# 05_-_SAMA7D65-MPU.net
KiCad netlist of a schematic drawn in Altium Designer
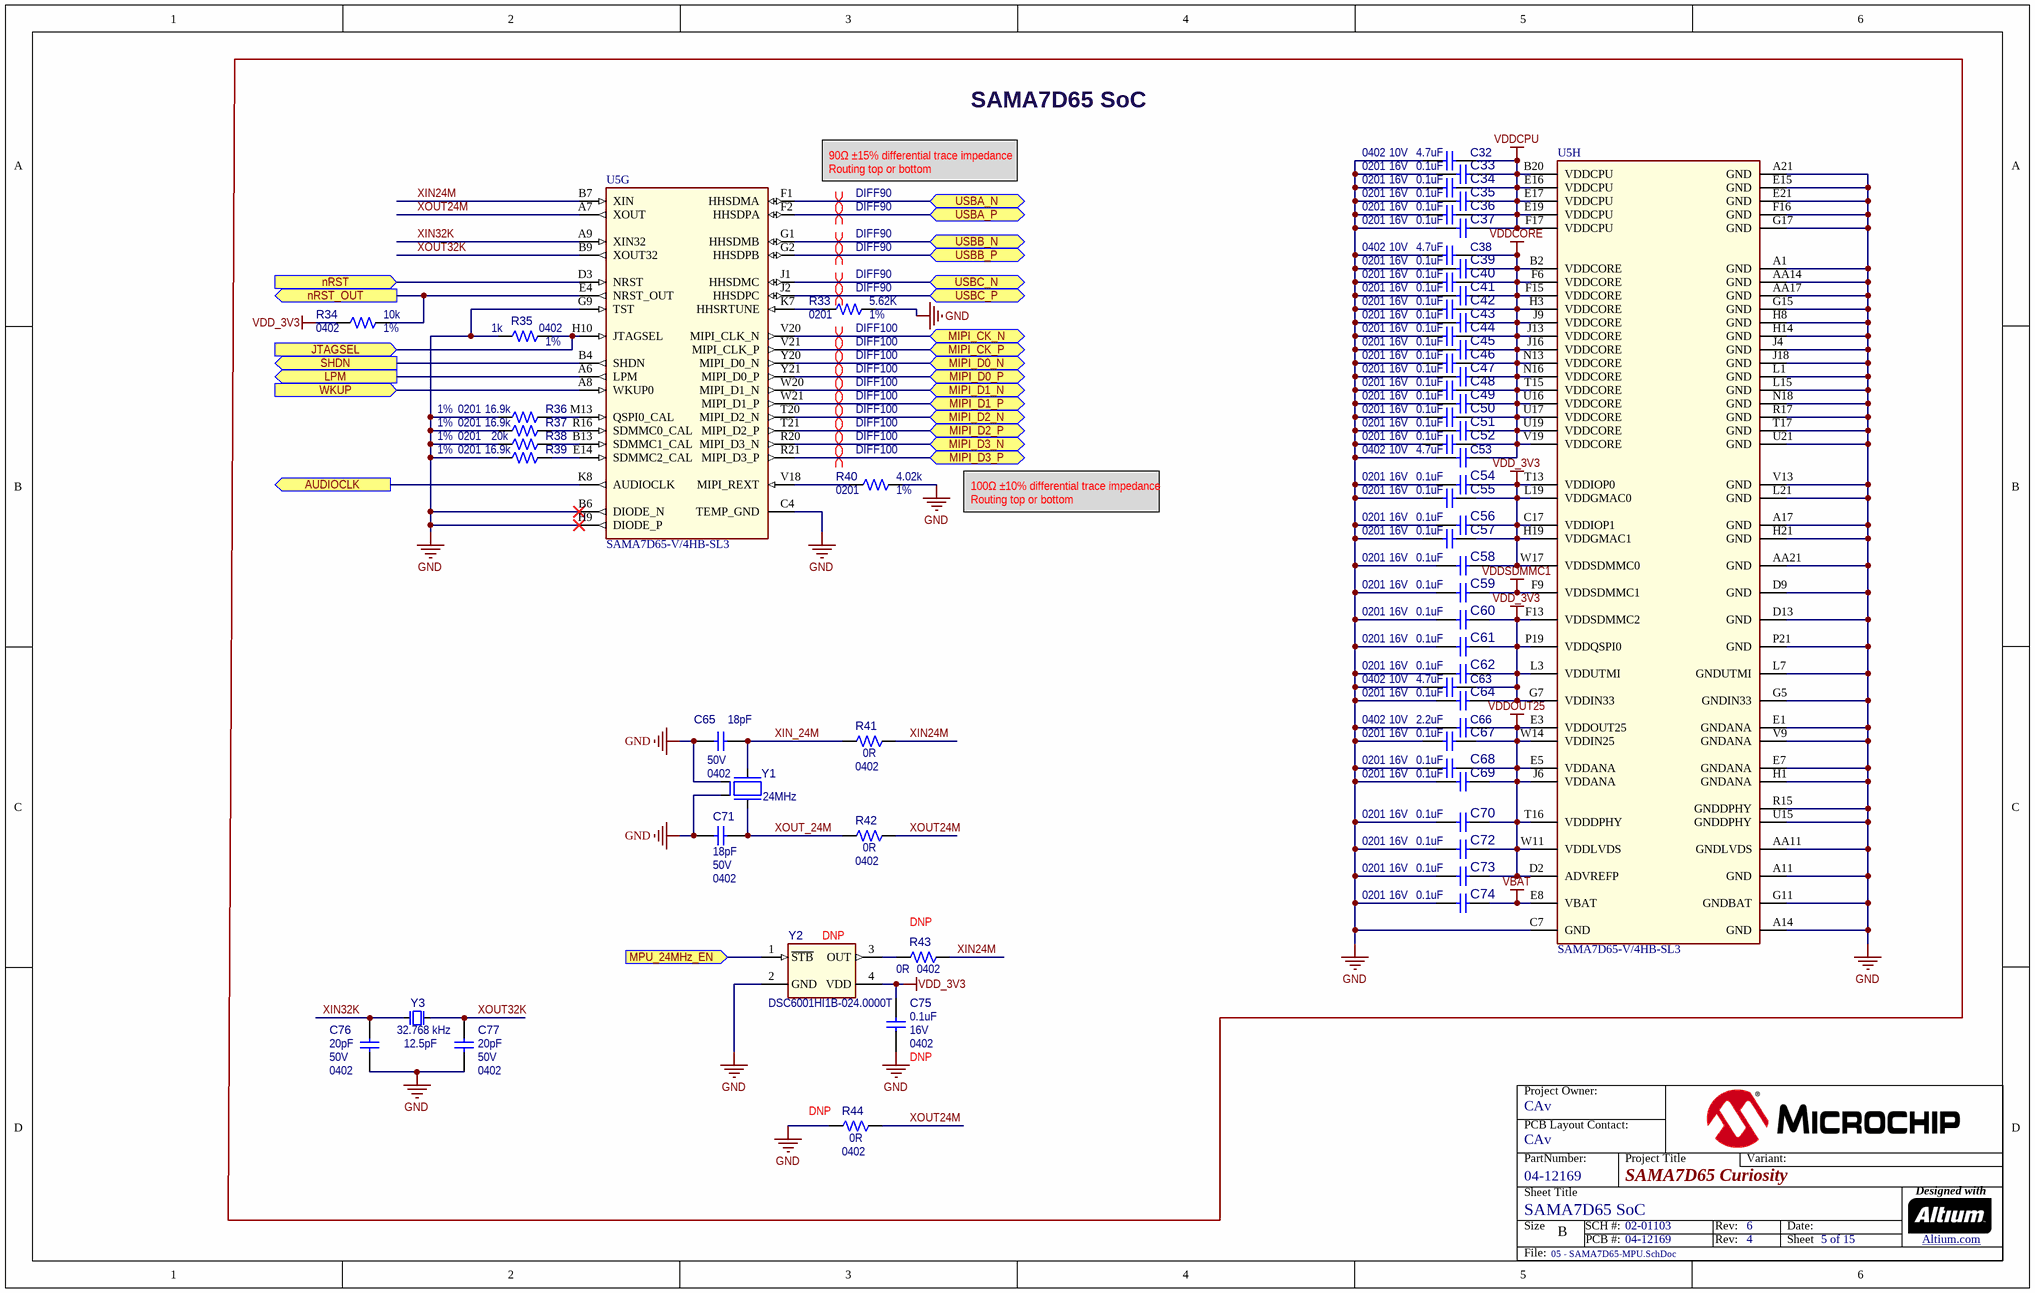
[diagram p0: 05 - SAMA7D65-MPU.SchDoc]

(export (version "E")
  (design (tool "Eeschema 10.0.6"))
  (components
    (comp (ref "C32")
      (value "4.7uF")
      (footprint "CAP_C_0402")
      (fields
        (field (name "VOLTAGE") "10V")
        (field (name "PACKAGE") "0402")
        (field (name "TOLERANCE") "10%")
        (field (name "Comment") "Capacitor NP")
        (field (name "OWNER") "Jesus Aviles")
      )
      (libsource (lib "MCHP-CDB") (part "Capacitor NP"))
    )
    (comp (ref "C33")
      (value "0.1uF")
      (footprint "CAP_C_0201")
      (fields
        (field (name "VOLTAGE") "16V")
        (field (name "PACKAGE") "0201")
        (field (name "TOLERANCE") "10%")
        (field (name "Comment") "Capacitor NP")
        (field (name "OWNER") "Dragos Danaila")
      )
      (libsource (lib "MCHP-CDB") (part "Capacitor NP"))
    )
    (comp (ref "C34")
      (value "0.1uF")
      (footprint "CAP_C_0201")
      (fields
        (field (name "VOLTAGE") "16V")
        (field (name "PACKAGE") "0201")
        (field (name "TOLERANCE") "10%")
        (field (name "Comment") "Capacitor NP")
        (field (name "OWNER") "Dragos Danaila")
      )
      (libsource (lib "MCHP-CDB") (part "Capacitor NP"))
    )
    (comp (ref "C35")
      (value "0.1uF")
      (footprint "CAP_C_0201")
      (fields
        (field (name "VOLTAGE") "16V")
        (field (name "PACKAGE") "0201")
        (field (name "TOLERANCE") "10%")
        (field (name "Comment") "Capacitor NP")
        (field (name "OWNER") "Dragos Danaila")
      )
      (libsource (lib "MCHP-CDB") (part "Capacitor NP"))
    )
    (comp (ref "C36")
      (value "0.1uF")
      (footprint "CAP_C_0201")
      (fields
        (field (name "VOLTAGE") "16V")
        (field (name "PACKAGE") "0201")
        (field (name "TOLERANCE") "10%")
        (field (name "Comment") "Capacitor NP")
        (field (name "OWNER") "Dragos Danaila")
      )
      (libsource (lib "MCHP-CDB") (part "Capacitor NP"))
    )
    (comp (ref "C37")
      (value "0.1uF")
      (footprint "CAP_C_0201")
      (fields
        (field (name "VOLTAGE") "16V")
        (field (name "PACKAGE") "0201")
        (field (name "TOLERANCE") "10%")
        (field (name "Comment") "Capacitor NP")
        (field (name "OWNER") "Dragos Danaila")
      )
      (libsource (lib "MCHP-CDB") (part "Capacitor NP"))
    )
    (comp (ref "C38")
      (value "4.7uF")
      (footprint "CAP_C_0402")
      (fields
        (field (name "VOLTAGE") "10V")
        (field (name "PACKAGE") "0402")
        (field (name "TOLERANCE") "10%")
        (field (name "Comment") "Capacitor NP")
        (field (name "OWNER") "Jesus Aviles")
      )
      (libsource (lib "MCHP-CDB") (part "Capacitor NP"))
    )
    (comp (ref "C39")
      (value "0.1uF")
      (footprint "CAP_C_0201")
      (fields
        (field (name "VOLTAGE") "16V")
        (field (name "PACKAGE") "0201")
        (field (name "TOLERANCE") "10%")
        (field (name "Comment") "Capacitor NP")
        (field (name "OWNER") "Dragos Danaila")
      )
      (libsource (lib "MCHP-CDB") (part "Capacitor NP"))
    )
    (comp (ref "C40")
      (value "0.1uF")
      (footprint "CAP_C_0201")
      (fields
        (field (name "VOLTAGE") "16V")
        (field (name "PACKAGE") "0201")
        (field (name "TOLERANCE") "10%")
        (field (name "Comment") "Capacitor NP")
        (field (name "OWNER") "Dragos Danaila")
      )
      (libsource (lib "MCHP-CDB") (part "Capacitor NP"))
    )
    (comp (ref "C41")
      (value "0.1uF")
      (footprint "CAP_C_0201")
      (fields
        (field (name "VOLTAGE") "16V")
        (field (name "PACKAGE") "0201")
        (field (name "TOLERANCE") "10%")
        (field (name "Comment") "Capacitor NP")
        (field (name "OWNER") "Dragos Danaila")
      )
      (libsource (lib "MCHP-CDB") (part "Capacitor NP"))
    )
    (comp (ref "C42")
      (value "0.1uF")
      (footprint "CAP_C_0201")
      (fields
        (field (name "VOLTAGE") "16V")
        (field (name "PACKAGE") "0201")
        (field (name "TOLERANCE") "10%")
        (field (name "Comment") "Capacitor NP")
        (field (name "OWNER") "Dragos Danaila")
      )
      (libsource (lib "MCHP-CDB") (part "Capacitor NP"))
    )
    (comp (ref "C43")
      (value "0.1uF")
      (footprint "CAP_C_0201")
      (fields
        (field (name "VOLTAGE") "16V")
        (field (name "PACKAGE") "0201")
        (field (name "TOLERANCE") "10%")
        (field (name "Comment") "Capacitor NP")
        (field (name "OWNER") "Dragos Danaila")
      )
      (libsource (lib "MCHP-CDB") (part "Capacitor NP"))
    )
    (comp (ref "C44")
      (value "0.1uF")
      (footprint "CAP_C_0201")
      (fields
        (field (name "VOLTAGE") "16V")
        (field (name "PACKAGE") "0201")
        (field (name "TOLERANCE") "10%")
        (field (name "Comment") "Capacitor NP")
        (field (name "OWNER") "Dragos Danaila")
      )
      (libsource (lib "MCHP-CDB") (part "Capacitor NP"))
    )
    (comp (ref "C45")
      (value "0.1uF")
      (footprint "CAP_C_0201")
      (fields
        (field (name "VOLTAGE") "16V")
        (field (name "PACKAGE") "0201")
        (field (name "TOLERANCE") "10%")
        (field (name "Comment") "Capacitor NP")
        (field (name "OWNER") "Dragos Danaila")
      )
      (libsource (lib "MCHP-CDB") (part "Capacitor NP"))
    )
    (comp (ref "C46")
      (value "0.1uF")
      (footprint "CAP_C_0201")
      (fields
        (field (name "VOLTAGE") "16V")
        (field (name "PACKAGE") "0201")
        (field (name "TOLERANCE") "10%")
        (field (name "Comment") "Capacitor NP")
        (field (name "OWNER") "Dragos Danaila")
      )
      (libsource (lib "MCHP-CDB") (part "Capacitor NP"))
    )
    (comp (ref "C47")
      (value "0.1uF")
      (footprint "CAP_C_0201")
      (fields
        (field (name "VOLTAGE") "16V")
        (field (name "PACKAGE") "0201")
        (field (name "TOLERANCE") "10%")
        (field (name "Comment") "Capacitor NP")
        (field (name "OWNER") "Dragos Danaila")
      )
      (libsource (lib "MCHP-CDB") (part "Capacitor NP"))
    )
    (comp (ref "C48")
      (value "0.1uF")
      (footprint "CAP_C_0201")
      (fields
        (field (name "VOLTAGE") "16V")
        (field (name "PACKAGE") "0201")
        (field (name "TOLERANCE") "10%")
        (field (name "Comment") "Capacitor NP")
        (field (name "OWNER") "Dragos Danaila")
      )
      (libsource (lib "MCHP-CDB") (part "Capacitor NP"))
    )
    (comp (ref "C49")
      (value "0.1uF")
      (footprint "CAP_C_0201")
      (fields
        (field (name "VOLTAGE") "16V")
        (field (name "PACKAGE") "0201")
        (field (name "TOLERANCE") "10%")
        (field (name "Comment") "Capacitor NP")
        (field (name "OWNER") "Dragos Danaila")
      )
      (libsource (lib "MCHP-CDB") (part "Capacitor NP"))
    )
    (comp (ref "C50")
      (value "0.1uF")
      (footprint "CAP_C_0201")
      (fields
        (field (name "VOLTAGE") "16V")
        (field (name "PACKAGE") "0201")
        (field (name "TOLERANCE") "10%")
        (field (name "Comment") "Capacitor NP")
        (field (name "OWNER") "Dragos Danaila")
      )
      (libsource (lib "MCHP-CDB") (part "Capacitor NP"))
    )
    (comp (ref "C51")
      (value "0.1uF")
      (footprint "CAP_C_0201")
      (fields
        (field (name "VOLTAGE") "16V")
        (field (name "PACKAGE") "0201")
        (field (name "TOLERANCE") "10%")
        (field (name "Comment") "Capacitor NP")
        (field (name "OWNER") "Dragos Danaila")
      )
      (libsource (lib "MCHP-CDB") (part "Capacitor NP"))
    )
    (comp (ref "C52")
      (value "0.1uF")
      (footprint "CAP_C_0201")
      (fields
        (field (name "VOLTAGE") "16V")
        (field (name "PACKAGE") "0201")
        (field (name "TOLERANCE") "10%")
        (field (name "Comment") "Capacitor NP")
        (field (name "OWNER") "Dragos Danaila")
      )
      (libsource (lib "MCHP-CDB") (part "Capacitor NP"))
    )
    (comp (ref "C53")
      (value "4.7uF")
      (footprint "CAP_C_0402")
      (fields
        (field (name "VOLTAGE") "10V")
        (field (name "PACKAGE") "0402")
        (field (name "TOLERANCE") "10%")
        (field (name "Comment") "Capacitor NP")
        (field (name "OWNER") "Jesus Aviles")
      )
      (libsource (lib "MCHP-CDB") (part "Capacitor NP"))
    )
    (comp (ref "C54")
      (value "0.1uF")
      (footprint "CAP_C_0201")
      (fields
        (field (name "VOLTAGE") "16V")
        (field (name "PACKAGE") "0201")
        (field (name "TOLERANCE") "10%")
        (field (name "Comment") "Capacitor NP")
        (field (name "OWNER") "Dragos Danaila")
      )
      (libsource (lib "MCHP-CDB") (part "Capacitor NP"))
    )
    (comp (ref "C55")
      (value "0.1uF")
      (footprint "CAP_C_0201")
      (fields
        (field (name "VOLTAGE") "16V")
        (field (name "PACKAGE") "0201")
        (field (name "TOLERANCE") "10%")
        (field (name "Comment") "Capacitor NP")
        (field (name "OWNER") "Dragos Danaila")
      )
      (libsource (lib "MCHP-CDB") (part "Capacitor NP"))
    )
    (comp (ref "C56")
      (value "0.1uF")
      (footprint "CAP_C_0201")
      (fields
        (field (name "VOLTAGE") "16V")
        (field (name "PACKAGE") "0201")
        (field (name "TOLERANCE") "10%")
        (field (name "Comment") "Capacitor NP")
        (field (name "OWNER") "Dragos Danaila")
      )
      (libsource (lib "MCHP-CDB") (part "Capacitor NP"))
    )
    (comp (ref "C57")
      (value "0.1uF")
      (footprint "CAP_C_0201")
      (fields
        (field (name "VOLTAGE") "16V")
        (field (name "PACKAGE") "0201")
        (field (name "TOLERANCE") "10%")
        (field (name "Comment") "Capacitor NP")
        (field (name "OWNER") "Dragos Danaila")
      )
      (libsource (lib "MCHP-CDB") (part "Capacitor NP"))
    )
    (comp (ref "C58")
      (value "0.1uF")
      (footprint "CAP_C_0201")
      (fields
        (field (name "VOLTAGE") "16V")
        (field (name "PACKAGE") "0201")
        (field (name "TOLERANCE") "10%")
        (field (name "Comment") "Capacitor NP")
        (field (name "OWNER") "Dragos Danaila")
      )
      (libsource (lib "MCHP-CDB") (part "Capacitor NP"))
    )
    (comp (ref "C59")
      (value "0.1uF")
      (footprint "CAP_C_0201")
      (fields
        (field (name "VOLTAGE") "16V")
        (field (name "PACKAGE") "0201")
        (field (name "TOLERANCE") "10%")
        (field (name "Comment") "Capacitor NP")
        (field (name "OWNER") "Dragos Danaila")
      )
      (libsource (lib "MCHP-CDB") (part "Capacitor NP"))
    )
    (comp (ref "C60")
      (value "0.1uF")
      (footprint "CAP_C_0201")
      (fields
        (field (name "VOLTAGE") "16V")
        (field (name "PACKAGE") "0201")
        (field (name "TOLERANCE") "10%")
        (field (name "Comment") "Capacitor NP")
        (field (name "OWNER") "Dragos Danaila")
      )
      (libsource (lib "MCHP-CDB") (part "Capacitor NP"))
    )
    (comp (ref "C61")
      (value "0.1uF")
      (footprint "CAP_C_0201")
      (fields
        (field (name "VOLTAGE") "16V")
        (field (name "PACKAGE") "0201")
        (field (name "TOLERANCE") "10%")
        (field (name "Comment") "Capacitor NP")
        (field (name "OWNER") "Dragos Danaila")
      )
      (libsource (lib "MCHP-CDB") (part "Capacitor NP"))
    )
    (comp (ref "C62")
      (value "0.1uF")
      (footprint "CAP_C_0201")
      (fields
        (field (name "VOLTAGE") "16V")
        (field (name "PACKAGE") "0201")
        (field (name "TOLERANCE") "10%")
        (field (name "Comment") "Capacitor NP")
        (field (name "OWNER") "Dragos Danaila")
      )
      (libsource (lib "MCHP-CDB") (part "Capacitor NP"))
    )
    (comp (ref "C63")
      (value "4.7uF")
      (footprint "CAP_C_0402")
      (fields
        (field (name "VOLTAGE") "10V")
        (field (name "PACKAGE") "0402")
        (field (name "TOLERANCE") "10%")
        (field (name "Comment") "Capacitor NP")
        (field (name "OWNER") "Jesus Aviles")
      )
      (libsource (lib "MCHP-CDB") (part "Capacitor NP"))
    )
    (comp (ref "C64")
      (value "0.1uF")
      (footprint "CAP_C_0201")
      (fields
        (field (name "VOLTAGE") "16V")
        (field (name "PACKAGE") "0201")
        (field (name "TOLERANCE") "10%")
        (field (name "Comment") "Capacitor NP")
        (field (name "OWNER") "Dragos Danaila")
      )
      (libsource (lib "MCHP-CDB") (part "Capacitor NP"))
    )
    (comp (ref "C65")
      (value "18pF")
      (footprint "CAP_C_0402")
      (fields
        (field (name "VOLTAGE") "50V")
        (field (name "PACKAGE") "0402")
        (field (name "TOLERANCE") "5%")
        (field (name "Comment") "Capacitor NP")
        (field (name "OWNER") "Tad Ahlvers")
      )
      (libsource (lib "MCHP-CDB") (part "Capacitor NP"))
    )
    (comp (ref "C66")
      (value "2.2uF")
      (footprint "CAP_C_0402")
      (fields
        (field (name "VOLTAGE") "10V")
        (field (name "PACKAGE") "0402")
        (field (name "TOLERANCE") "10%")
        (field (name "Comment") "Capacitor NP")
        (field (name "OWNER") "Pilar Alcaine")
      )
      (libsource (lib "MCHP-CDB") (part "Capacitor NP"))
    )
    (comp (ref "C67")
      (value "0.1uF")
      (footprint "CAP_C_0201")
      (fields
        (field (name "VOLTAGE") "16V")
        (field (name "PACKAGE") "0201")
        (field (name "TOLERANCE") "10%")
        (field (name "Comment") "Capacitor NP")
        (field (name "OWNER") "Dragos Danaila")
      )
      (libsource (lib "MCHP-CDB") (part "Capacitor NP"))
    )
    (comp (ref "C68")
      (value "0.1uF")
      (footprint "CAP_C_0201")
      (fields
        (field (name "VOLTAGE") "16V")
        (field (name "PACKAGE") "0201")
        (field (name "TOLERANCE") "10%")
        (field (name "Comment") "Capacitor NP")
        (field (name "OWNER") "Dragos Danaila")
      )
      (libsource (lib "MCHP-CDB") (part "Capacitor NP"))
    )
    (comp (ref "C69")
      (value "0.1uF")
      (footprint "CAP_C_0201")
      (fields
        (field (name "VOLTAGE") "16V")
        (field (name "PACKAGE") "0201")
        (field (name "TOLERANCE") "10%")
        (field (name "Comment") "Capacitor NP")
        (field (name "OWNER") "Dragos Danaila")
      )
      (libsource (lib "MCHP-CDB") (part "Capacitor NP"))
    )
    (comp (ref "C70")
      (value "0.1uF")
      (footprint "CAP_C_0201")
      (fields
        (field (name "VOLTAGE") "16V")
        (field (name "PACKAGE") "0201")
        (field (name "TOLERANCE") "10%")
        (field (name "Comment") "Capacitor NP")
        (field (name "OWNER") "Dragos Danaila")
      )
      (libsource (lib "MCHP-CDB") (part "Capacitor NP"))
    )
    (comp (ref "C71")
      (value "18pF")
      (footprint "CAP_C_0402")
      (fields
        (field (name "VOLTAGE") "50V")
        (field (name "PACKAGE") "0402")
        (field (name "TOLERANCE") "5%")
        (field (name "Comment") "Capacitor NP")
        (field (name "OWNER") "Tad Ahlvers")
      )
      (libsource (lib "MCHP-CDB") (part "Capacitor NP"))
    )
    (comp (ref "C72")
      (value "0.1uF")
      (footprint "CAP_C_0201")
      (fields
        (field (name "VOLTAGE") "16V")
        (field (name "PACKAGE") "0201")
        (field (name "TOLERANCE") "10%")
        (field (name "Comment") "Capacitor NP")
        (field (name "OWNER") "Dragos Danaila")
      )
      (libsource (lib "MCHP-CDB") (part "Capacitor NP"))
    )
    (comp (ref "C73")
      (value "0.1uF")
      (footprint "CAP_C_0201")
      (fields
        (field (name "VOLTAGE") "16V")
        (field (name "PACKAGE") "0201")
        (field (name "TOLERANCE") "10%")
        (field (name "Comment") "Capacitor NP")
        (field (name "OWNER") "Dragos Danaila")
      )
      (libsource (lib "MCHP-CDB") (part "Capacitor NP"))
    )
    (comp (ref "C74")
      (value "0.1uF")
      (footprint "CAP_C_0201")
      (fields
        (field (name "VOLTAGE") "16V")
        (field (name "PACKAGE") "0201")
        (field (name "TOLERANCE") "10%")
        (field (name "Comment") "Capacitor NP")
        (field (name "OWNER") "Dragos Danaila")
      )
      (libsource (lib "MCHP-CDB") (part "Capacitor NP"))
    )
    (comp (ref "C75")
      (value "0.1uF")
      (footprint "CAP_C_0402")
      (fields
        (field (name "VOLTAGE") "16V")
        (field (name "PACKAGE") "0402")
        (field (name "TOLERANCE") "10%")
        (field (name "POPULATED") "DNP")
        (field (name "Comment") "Capacitor NP")
        (field (name "OWNER") "Sompoch Loboonlert")
      )
      (libsource (lib "MCHP-CDB") (part "Capacitor NP"))
    )
    (comp (ref "C76")
      (value "20pF")
      (footprint "CAP_C_0402")
      (fields
        (field (name "VOLTAGE") "50V")
        (field (name "PACKAGE") "0402")
        (field (name "TOLERANCE") "5%")
        (field (name "Comment") "Capacitor NP")
      )
      (libsource (lib "MCHP-CDB") (part "Capacitor NP"))
    )
    (comp (ref "C77")
      (value "20pF")
      (footprint "CAP_C_0402")
      (fields
        (field (name "VOLTAGE") "50V")
        (field (name "PACKAGE") "0402")
        (field (name "TOLERANCE") "5%")
        (field (name "Comment") "Capacitor NP")
      )
      (libsource (lib "MCHP-CDB") (part "Capacitor NP"))
    )
    (comp (ref "R33")
      (value "5.62K")
      (footprint "RES_C_0201")
      (description "Resistor")
      (fields
        (field (name "PACKAGE") "0201")
        (field (name "TOLERANCE") "1%")
        (field (name "POWER") "1/20W")
        (field (name "OWNER") "Ilie Galan")
      )
      (libsource (lib "MCHP-CDB") (part "Resistor"))
    )
    (comp (ref "R34")
      (value "10k")
      (footprint "RES_C_0402")
      (description "Resistor")
      (fields
        (field (name "PACKAGE") "0402")
        (field (name "TOLERANCE") "1%")
        (field (name "VOLTAGE") "50V")
        (field (name "POWER") "1/10W")
        (field (name "OWNER") "Brent Lanphear")
      )
      (libsource (lib "MCHP-CDB") (part "Resistor"))
    )
    (comp (ref "R35")
      (value "1k")
      (footprint "RES_C_0402")
      (description "Resistor")
      (fields
        (field (name "PACKAGE") "0402")
        (field (name "TOLERANCE") "1%")
        (field (name "VOLTAGE") "50V")
        (field (name "POWER") "1/10W")
        (field (name "OWNER") "Tad Ahlvers")
      )
      (libsource (lib "MCHP-CDB") (part "Resistor"))
    )
    (comp (ref "R36")
      (value "16.9k")
      (footprint "RES_C_0201")
      (description "Resistor")
      (fields
        (field (name "PACKAGE") "0201")
        (field (name "TOLERANCE") "1%")
        (field (name "POWER") "1/20W")
        (field (name "VOLTAGE") "25V")
        (field (name "OWNER") "Dragos Danaila")
      )
      (libsource (lib "MCHP-CDB") (part "Resistor"))
    )
    (comp (ref "R37")
      (value "16.9k")
      (footprint "RES_C_0201")
      (description "Resistor")
      (fields
        (field (name "PACKAGE") "0201")
        (field (name "TOLERANCE") "1%")
        (field (name "POWER") "1/20W")
        (field (name "VOLTAGE") "25V")
        (field (name "OWNER") "Dragos Danaila")
      )
      (libsource (lib "MCHP-CDB") (part "Resistor"))
    )
    (comp (ref "R38")
      (value "20k")
      (footprint "RES_C_0201")
      (description "Resistor")
      (fields
        (field (name "PACKAGE") "0201")
        (field (name "TOLERANCE") "1%")
        (field (name "POWER") "1/20W")
        (field (name "OWNER") "Ilie Galan")
      )
      (libsource (lib "MCHP-CDB") (part "Resistor"))
    )
    (comp (ref "R39")
      (value "16.9k")
      (footprint "RES_C_0201")
      (description "Resistor")
      (fields
        (field (name "PACKAGE") "0201")
        (field (name "TOLERANCE") "1%")
        (field (name "POWER") "1/20W")
        (field (name "VOLTAGE") "25V")
        (field (name "OWNER") "Dragos Danaila")
      )
      (libsource (lib "MCHP-CDB") (part "Resistor"))
    )
    (comp (ref "R40")
      (value "4.02k")
      (footprint "RES_C_0201")
      (description "Resistor")
      (fields
        (field (name "PACKAGE") "0201")
        (field (name "TOLERANCE") "1%")
        (field (name "POWER") "1/20W")
        (field (name "OWNER") "Ilie Galan")
      )
      (libsource (lib "MCHP-CDB") (part "Resistor"))
    )
    (comp (ref "R41")
      (value "0R")
      (footprint "RES_C_0402")
      (description "Resistor")
      (fields
        (field (name "PACKAGE") "0402")
        (field (name "POWER") "1/16W")
        (field (name "OWNER") "Sompoch Loboonlert")
      )
      (libsource (lib "MCHP-CDB") (part "Resistor"))
    )
    (comp (ref "R42")
      (value "0R")
      (footprint "RES_C_0402")
      (description "Resistor")
      (fields
        (field (name "PACKAGE") "0402")
        (field (name "POWER") "1/16W")
        (field (name "OWNER") "Sompoch Loboonlert")
      )
      (libsource (lib "MCHP-CDB") (part "Resistor"))
    )
    (comp (ref "R43")
      (value "0R")
      (footprint "RES_C_0402")
      (description "Resistor")
      (fields
        (field (name "PACKAGE") "0402")
        (field (name "POWER") "1/16W")
        (field (name "POPULATED") "DNP")
        (field (name "OWNER") "Sompoch Loboonlert")
      )
      (libsource (lib "MCHP-CDB") (part "Resistor"))
    )
    (comp (ref "R44")
      (value "0R")
      (footprint "RES_C_0402")
      (description "Resistor")
      (fields
        (field (name "PACKAGE") "0402")
        (field (name "POWER") "1/16W")
        (field (name "POPULATED") "DNP")
        (field (name "OWNER") "Sompoch Loboonlert")
      )
      (libsource (lib "MCHP-CDB") (part "Resistor"))
    )
    (comp (ref "U5")
      (value "SAMA7D65-V/4HB-SL3")
      (footprint "TFBGA-343_14x14")
      (description "SAMA7D65 MPU 1000MHz Cortex-A7 TFBGA-343")
      (fields (field (name "Comment") "SAMA7D65") (field (name "OWNER") "Ciprian Abramov"))
      (libsource (lib "MCHP-CDB") (part "SAMA7D65-TFBGA-343"))
    )
    (comp (ref "Y1")
      (value "24MHz")
      (footprint "CRYSTAL_L2.0W1.6H0.5_FA-128")
      (fields
        (field (name "TOLERANCE") "20ppm")
        (field (name "Comment") "Crystal 4 Pins")
        (field (name "OWNER") "Ciprian Abramov")
      )
      (libsource (lib "MCHP-CDB") (part "Crystal 4 Pins"))
    )
    (comp (ref "Y2")
      (value "DSC60xx DFN-4_LGA-4")
      (footprint "DFN-4_VFLGA_1.6 X 1.2")
      (fields
        (field (name "MANUFACTURER PART NUMBER 1") "DSC6001HI1B-024.0000T")
        (field (name "POPULATED") "DNP")
        (field (name "OWNER") "Ciprian Abramov")
      )
      (libsource (lib "MCHP-CDB") (part "DSC60xx DFN-4_LGA-4"))
    )
    (comp (ref "Y3")
      (value "32.768 kHz")
      (footprint "CRYSTAL_FC-12M_L2.05W1.2H0.6")
      (description "Crystal")
      (fields
        (field (name "TOLERANCE") "20ppm")
        (field (name "LOAD CAPACITANCE") "12.5pF")
        (field (name "Comment") "Crystal 2 Pins")
        (field (name "OWNER") "Dragos Danaila")
      )
      (libsource (lib "MCHP-CDB") (part "Crystal 2 Pins"))
    )
  )
  (nets
    (net (code "1") (name "/AUDIOCLK") (class "Default")
      (node (ref "U5") (pin "K8") (pinfunction "AUDIOCLK_K8") (pintype "output"))
    )
    (net (code "2") (name "/JTAGSEL") (class "Default")
      (node (ref "R35") (pin "1") (pinfunction "1_1") (pintype "passive"))
      (node (ref "U5") (pin "H10") (pinfunction "JTAGSEL_H10") (pintype "input"))
    )
    (net (code "3") (name "/LPM") (class "Default")
      (node (ref "U5") (pin "A6") (pinfunction "LPM_A6") (pintype "output"))
    )
    (net (code "4") (name "/MIPI_CK_N") (class "Default")
      (node (ref "U5") (pin "V20") (pinfunction "MIPI_CLK_N_V20") (pintype "output"))
    )
    (net (code "5") (name "/MIPI_CK_P") (class "Default")
      (node (ref "U5") (pin "V21") (pinfunction "MIPI_CLK_P_V21") (pintype "output"))
    )
    (net (code "6") (name "/MIPI_D0_N") (class "Default")
      (node (ref "U5") (pin "Y20") (pinfunction "MIPI_D0_N_Y20") (pintype "output"))
    )
    (net (code "7") (name "/MIPI_D0_P") (class "Default")
      (node (ref "U5") (pin "Y21") (pinfunction "MIPI_D0_P_Y21") (pintype "output"))
    )
    (net (code "8") (name "/MIPI_D1_N") (class "Default")
      (node (ref "U5") (pin "W20") (pinfunction "MIPI_D1_N_W20") (pintype "output"))
    )
    (net (code "9") (name "/MIPI_D1_P") (class "Default")
      (node (ref "U5") (pin "W21") (pinfunction "MIPI_D1_P_W21") (pintype "output"))
    )
    (net (code "10") (name "/MIPI_D2_N") (class "Default")
      (node (ref "U5") (pin "T20") (pinfunction "MIPI_D2_N_T20") (pintype "output"))
    )
    (net (code "11") (name "/MIPI_D2_P") (class "Default")
      (node (ref "U5") (pin "T21") (pinfunction "MIPI_D2_P_T21") (pintype "output"))
    )
    (net (code "12") (name "/MIPI_D3_N") (class "Default")
      (node (ref "U5") (pin "R20") (pinfunction "MIPI_D3_N_R20") (pintype "output"))
    )
    (net (code "13") (name "/MIPI_D3_P") (class "Default")
      (node (ref "U5") (pin "R21") (pinfunction "MIPI_D3_P_R21") (pintype "output"))
    )
    (net (code "14") (name "/MPU_24MHz_EN") (class "Default")
      (node (ref "Y2") (pin "1") (pinfunction "~{STB}_1") (pintype "input"))
    )
    (net (code "15") (name "/SHDN") (class "Default")
      (node (ref "U5") (pin "B4") (pinfunction "SHDN_B4") (pintype "output"))
    )
    (net (code "16") (name "/USBA_N") (class "Default")
      (node (ref "U5") (pin "F1") (pinfunction "HHSDMA_F1") (pintype "bidirectional"))
    )
    (net (code "17") (name "/USBA_P") (class "Default")
      (node (ref "U5") (pin "F2") (pinfunction "HHSDPA_F2") (pintype "bidirectional"))
    )
    (net (code "18") (name "/USBB_N") (class "Default")
      (node (ref "U5") (pin "G1") (pinfunction "HHSDMB_G1") (pintype "bidirectional"))
    )
    (net (code "19") (name "/USBB_P") (class "Default")
      (node (ref "U5") (pin "G2") (pinfunction "HHSDPB_G2") (pintype "bidirectional"))
    )
    (net (code "20") (name "/USBC_N") (class "Default")
      (node (ref "U5") (pin "J1") (pinfunction "HHSDMC_J1") (pintype "bidirectional"))
    )
    (net (code "21") (name "/USBC_P") (class "Default")
      (node (ref "U5") (pin "J2") (pinfunction "HHSDPC_J2") (pintype "bidirectional"))
    )
    (net (code "22") (name "/WKUP") (class "Default")
      (node (ref "U5") (pin "A8") (pinfunction "WKUP0_A8") (pintype "input"))
    )
    (net (code "23") (name "/XIN24M") (class "Default")
      (node (ref "R41") (pin "2") (pinfunction "2_2") (pintype "passive"))
      (node (ref "R43") (pin "2") (pinfunction "2_2") (pintype "passive"))
      (node (ref "U5") (pin "B7") (pinfunction "XIN_B7") (pintype "input"))
    )
    (net (code "24") (name "/XIN32K") (class "Default")
      (node (ref "C76") (pin "1") (pinfunction "1_1") (pintype "passive"))
      (node (ref "U5") (pin "A9") (pinfunction "XIN32_A9") (pintype "input"))
      (node (ref "Y3") (pin "1") (pinfunction "Osc1_1") (pintype "passive"))
    )
    (net (code "25") (name "/XIN_24M") (class "Default")
      (node (ref "C65") (pin "1") (pinfunction "1_1") (pintype "passive"))
      (node (ref "R41") (pin "1") (pinfunction "1_1") (pintype "passive"))
      (node (ref "Y1") (pin "1") (pinfunction "Osc1_1") (pintype "passive"))
    )
    (net (code "26") (name "/XOUT24M") (class "Default")
      (node (ref "R42") (pin "2") (pinfunction "2_2") (pintype "passive"))
      (node (ref "R44") (pin "2") (pinfunction "2_2") (pintype "passive"))
      (node (ref "U5") (pin "A7") (pinfunction "XOUT_A7") (pintype "output"))
    )
    (net (code "27") (name "/XOUT32K") (class "Default")
      (node (ref "C77") (pin "1") (pinfunction "1_1") (pintype "passive"))
      (node (ref "U5") (pin "B9") (pinfunction "XOUT32_B9") (pintype "output"))
      (node (ref "Y3") (pin "2") (pinfunction "Osc2_2") (pintype "passive"))
    )
    (net (code "28") (name "/XOUT_24M") (class "Default")
      (node (ref "C71") (pin "1") (pinfunction "1_1") (pintype "passive"))
      (node (ref "R42") (pin "1") (pinfunction "1_1") (pintype "passive"))
      (node (ref "Y1") (pin "3") (pinfunction "Osc2_3") (pintype "passive"))
    )
    (net (code "29") (name "/nRST") (class "Default")
      (node (ref "U5") (pin "D3") (pinfunction "NRST_D3") (pintype "input"))
    )
    (net (code "30") (name "/nRST_OUT") (class "Default")
      (node (ref "R34") (pin "2") (pinfunction "2_2") (pintype "passive"))
      (node (ref "U5") (pin "E4") (pinfunction "NRST_OUT_E4") (pintype "output"))
    )
    (net (code "31") (name "GND") (class "Default")
      (node (ref "C32") (pin "2") (pinfunction "2_2") (pintype "passive"))
      (node (ref "C33") (pin "2") (pinfunction "2_2") (pintype "passive"))
      (node (ref "C34") (pin "2") (pinfunction "2_2") (pintype "passive"))
      (node (ref "C35") (pin "2") (pinfunction "2_2") (pintype "passive"))
      (node (ref "C36") (pin "2") (pinfunction "2_2") (pintype "passive"))
      (node (ref "C37") (pin "2") (pinfunction "2_2") (pintype "passive"))
      (node (ref "C38") (pin "2") (pinfunction "2_2") (pintype "passive"))
      (node (ref "C39") (pin "2") (pinfunction "2_2") (pintype "passive"))
      (node (ref "C40") (pin "2") (pinfunction "2_2") (pintype "passive"))
      (node (ref "C41") (pin "2") (pinfunction "2_2") (pintype "passive"))
      (node (ref "C42") (pin "2") (pinfunction "2_2") (pintype "passive"))
      (node (ref "C43") (pin "2") (pinfunction "2_2") (pintype "passive"))
      (node (ref "C44") (pin "2") (pinfunction "2_2") (pintype "passive"))
      (node (ref "C45") (pin "2") (pinfunction "2_2") (pintype "passive"))
      (node (ref "C46") (pin "2") (pinfunction "2_2") (pintype "passive"))
      (node (ref "C47") (pin "2") (pinfunction "2_2") (pintype "passive"))
      (node (ref "C48") (pin "2") (pinfunction "2_2") (pintype "passive"))
      (node (ref "C49") (pin "2") (pinfunction "2_2") (pintype "passive"))
      (node (ref "C50") (pin "2") (pinfunction "2_2") (pintype "passive"))
      (node (ref "C51") (pin "2") (pinfunction "2_2") (pintype "passive"))
      (node (ref "C52") (pin "2") (pinfunction "2_2") (pintype "passive"))
      (node (ref "C53") (pin "2") (pinfunction "2_2") (pintype "passive"))
      (node (ref "C54") (pin "2") (pinfunction "2_2") (pintype "passive"))
      (node (ref "C55") (pin "2") (pinfunction "2_2") (pintype "passive"))
      (node (ref "C56") (pin "2") (pinfunction "2_2") (pintype "passive"))
      (node (ref "C57") (pin "2") (pinfunction "2_2") (pintype "passive"))
      (node (ref "C58") (pin "2") (pinfunction "2_2") (pintype "passive"))
      (node (ref "C59") (pin "2") (pinfunction "2_2") (pintype "passive"))
      (node (ref "C60") (pin "2") (pinfunction "2_2") (pintype "passive"))
      (node (ref "C61") (pin "2") (pinfunction "2_2") (pintype "passive"))
      (node (ref "C62") (pin "2") (pinfunction "2_2") (pintype "passive"))
      (node (ref "C63") (pin "1") (pinfunction "1_1") (pintype "passive"))
      (node (ref "C64") (pin "2") (pinfunction "2_2") (pintype "passive"))
      (node (ref "C65") (pin "2") (pinfunction "2_2") (pintype "passive"))
      (node (ref "C66") (pin "1") (pinfunction "1_1") (pintype "passive"))
      (node (ref "C67") (pin "2") (pinfunction "2_2") (pintype "passive"))
      (node (ref "C68") (pin "2") (pinfunction "2_2") (pintype "passive"))
      (node (ref "C69") (pin "2") (pinfunction "2_2") (pintype "passive"))
      (node (ref "C70") (pin "2") (pinfunction "2_2") (pintype "passive"))
      (node (ref "C71") (pin "2") (pinfunction "2_2") (pintype "passive"))
      (node (ref "C72") (pin "2") (pinfunction "2_2") (pintype "passive"))
      (node (ref "C73") (pin "2") (pinfunction "2_2") (pintype "passive"))
      (node (ref "C74") (pin "2") (pinfunction "2_2") (pintype "passive"))
      (node (ref "C75") (pin "1") (pinfunction "1_1") (pintype "passive"))
      (node (ref "C76") (pin "2") (pinfunction "2_2") (pintype "passive"))
      (node (ref "C77") (pin "2") (pinfunction "2_2") (pintype "passive"))
      (node (ref "R33") (pin "2") (pinfunction "2_2") (pintype "passive"))
      (node (ref "R35") (pin "2") (pinfunction "2_2") (pintype "passive"))
      (node (ref "R36") (pin "1") (pinfunction "1_1") (pintype "passive"))
      (node (ref "R37") (pin "1") (pinfunction "1_1") (pintype "passive"))
      (node (ref "R38") (pin "1") (pinfunction "1_1") (pintype "passive"))
      (node (ref "R39") (pin "1") (pinfunction "1_1") (pintype "passive"))
      (node (ref "R40") (pin "2") (pinfunction "2_2") (pintype "passive"))
      (node (ref "R44") (pin "1") (pinfunction "1_1") (pintype "passive"))
      (node (ref "U5") (pin "A1") (pinfunction "GND_A1") (pintype "power_in"))
      (node (ref "U5") (pin "A11") (pinfunction "GND_A11") (pintype "power_in"))
      (node (ref "U5") (pin "A14") (pinfunction "GND_A14") (pintype "power_in"))
      (node (ref "U5") (pin "A17") (pinfunction "GND_A17") (pintype "power_in"))
      (node (ref "U5") (pin "A21") (pinfunction "GND_A21") (pintype "power_in"))
      (node (ref "U5") (pin "AA11") (pinfunction "GNDLVDS_AA11") (pintype "power_in"))
      (node (ref "U5") (pin "AA14") (pinfunction "GND_AA14") (pintype "power_in"))
      (node (ref "U5") (pin "AA17") (pinfunction "GND_AA17") (pintype "power_in"))
      (node (ref "U5") (pin "AA21") (pinfunction "GND_AA21") (pintype "power_in"))
      (node (ref "U5") (pin "B6") (pinfunction "DIODE_N_B6") (pintype "output"))
      (node (ref "U5") (pin "C4") (pinfunction "TEMP_GND_C4") (pintype "passive"))
      (node (ref "U5") (pin "C7") (pinfunction "GND_C7") (pintype "power_in"))
      (node (ref "U5") (pin "D13") (pinfunction "GND_D13") (pintype "power_in"))
      (node (ref "U5") (pin "D9") (pinfunction "GND_D9") (pintype "power_in"))
      (node (ref "U5") (pin "E1") (pinfunction "GNDANA_E1") (pintype "power_in"))
      (node (ref "U5") (pin "E15") (pinfunction "GND_E15") (pintype "power_in"))
      (node (ref "U5") (pin "E21") (pinfunction "GND_E21") (pintype "power_in"))
      (node (ref "U5") (pin "E7") (pinfunction "GNDANA_E7") (pintype "power_in"))
      (node (ref "U5") (pin "F16") (pinfunction "GND_F16") (pintype "power_in"))
      (node (ref "U5") (pin "G11") (pinfunction "GNDBAT_G11") (pintype "power_in"))
      (node (ref "U5") (pin "G15") (pinfunction "GND_G15") (pintype "power_in"))
      (node (ref "U5") (pin "G17") (pinfunction "GND_G17") (pintype "power_in"))
      (node (ref "U5") (pin "G5") (pinfunction "GNDIN33_G5") (pintype "power_in"))
      (node (ref "U5") (pin "G9") (pinfunction "TST_G9") (pintype "input"))
      (node (ref "U5") (pin "H1") (pinfunction "GNDANA_H1") (pintype "power_in"))
      (node (ref "U5") (pin "H14") (pinfunction "GND_H14") (pintype "power_in"))
      (node (ref "U5") (pin "H21") (pinfunction "GND_H21") (pintype "power_in"))
      (node (ref "U5") (pin "H8") (pinfunction "GND_H8") (pintype "power_in"))
      (node (ref "U5") (pin "H9") (pinfunction "DIODE_P_H9") (pintype "output"))
      (node (ref "U5") (pin "J18") (pinfunction "GND_J18") (pintype "power_in"))
      (node (ref "U5") (pin "J4") (pinfunction "GND_J4") (pintype "power_in"))
      (node (ref "U5") (pin "L1") (pinfunction "GND_L1") (pintype "power_in"))
      (node (ref "U5") (pin "L15") (pinfunction "GND_L15") (pintype "power_in"))
      (node (ref "U5") (pin "L21") (pinfunction "GND_L21") (pintype "power_in"))
      (node (ref "U5") (pin "L7") (pinfunction "GNDUTMI_L7") (pintype "power_in"))
      (node (ref "U5") (pin "N18") (pinfunction "GND_N18") (pintype "power_in"))
      (node (ref "U5") (pin "P21") (pinfunction "GND_P21") (pintype "power_in"))
      (node (ref "U5") (pin "R15") (pinfunction "GNDDPHY_R15") (pintype "power_in"))
      (node (ref "U5") (pin "R17") (pinfunction "GND_R17") (pintype "power_in"))
      (node (ref "U5") (pin "T17") (pinfunction "GND_T17") (pintype "power_in"))
      (node (ref "U5") (pin "U15") (pinfunction "GNDDPHY_U15") (pintype "power_in"))
      (node (ref "U5") (pin "U21") (pinfunction "GND_U21") (pintype "power_in"))
      (node (ref "U5") (pin "V13") (pinfunction "GND_V13") (pintype "power_in"))
      (node (ref "U5") (pin "V9") (pinfunction "GNDANA_V9") (pintype "power_in"))
      (node (ref "Y1") (pin "2") (pinfunction "GND_2") (pintype "power_in"))
      (node (ref "Y1") (pin "4") (pinfunction "GND_4") (pintype "power_in"))
      (node (ref "Y2") (pin "2") (pinfunction "GND_2") (pintype "power_in"))
    )
    (net (code "32") (name "Net-(U5G-HHSRTUNE)") (class "Default")
      (node (ref "R33") (pin "1") (pinfunction "1_1") (pintype "passive"))
      (node (ref "U5") (pin "K7") (pinfunction "HHSRTUNE_K7") (pintype "input"))
    )
    (net (code "33") (name "Net-(U5G-MIPI_REXT)") (class "Default")
      (node (ref "R40") (pin "1") (pinfunction "1_1") (pintype "passive"))
      (node (ref "U5") (pin "V18") (pinfunction "MIPI_REXT_V18") (pintype "input"))
    )
    (net (code "34") (name "Net-(U5G-QSPI0_CAL)") (class "Default")
      (node (ref "R36") (pin "2") (pinfunction "2_2") (pintype "passive"))
      (node (ref "U5") (pin "M13") (pinfunction "QSPI0_CAL_M13") (pintype "input"))
    )
    (net (code "35") (name "Net-(U5G-SDMMC0_CAL)") (class "Default")
      (node (ref "R37") (pin "2") (pinfunction "2_2") (pintype "passive"))
      (node (ref "U5") (pin "R16") (pinfunction "SDMMC0_CAL_R16") (pintype "input"))
    )
    (net (code "36") (name "Net-(U5G-SDMMC1_CAL)") (class "Default")
      (node (ref "R38") (pin "2") (pinfunction "2_2") (pintype "passive"))
      (node (ref "U5") (pin "B13") (pinfunction "SDMMC1_CAL_B13") (pintype "input"))
    )
    (net (code "37") (name "Net-(U5G-SDMMC2_CAL)") (class "Default")
      (node (ref "R39") (pin "2") (pinfunction "2_2") (pintype "passive"))
      (node (ref "U5") (pin "E14") (pinfunction "SDMMC2_CAL_E14") (pintype "input"))
    )
    (net (code "38") (name "Net-(Y2-OUT)") (class "Default")
      (node (ref "R43") (pin "1") (pinfunction "1_1") (pintype "passive"))
      (node (ref "Y2") (pin "3") (pinfunction "OUT_3") (pintype "output"))
    )
    (net (code "39") (name "VBAT") (class "Default")
      (node (ref "C74") (pin "1") (pinfunction "1_1") (pintype "passive"))
      (node (ref "U5") (pin "E8") (pinfunction "VBAT_E8") (pintype "power_in"))
    )
    (net (code "40") (name "VDDCORE") (class "Default")
      (node (ref "C38") (pin "1") (pinfunction "1_1") (pintype "passive"))
      (node (ref "C39") (pin "1") (pinfunction "1_1") (pintype "passive"))
      (node (ref "C40") (pin "1") (pinfunction "1_1") (pintype "passive"))
      (node (ref "C41") (pin "1") (pinfunction "1_1") (pintype "passive"))
      (node (ref "C42") (pin "1") (pinfunction "1_1") (pintype "passive"))
      (node (ref "C43") (pin "1") (pinfunction "1_1") (pintype "passive"))
      (node (ref "C44") (pin "1") (pinfunction "1_1") (pintype "passive"))
      (node (ref "C45") (pin "1") (pinfunction "1_1") (pintype "passive"))
      (node (ref "C46") (pin "1") (pinfunction "1_1") (pintype "passive"))
      (node (ref "C47") (pin "1") (pinfunction "1_1") (pintype "passive"))
      (node (ref "C48") (pin "1") (pinfunction "1_1") (pintype "passive"))
      (node (ref "C49") (pin "1") (pinfunction "1_1") (pintype "passive"))
      (node (ref "C50") (pin "1") (pinfunction "1_1") (pintype "passive"))
      (node (ref "C51") (pin "1") (pinfunction "1_1") (pintype "passive"))
      (node (ref "C52") (pin "1") (pinfunction "1_1") (pintype "passive"))
      (node (ref "C53") (pin "1") (pinfunction "1_1") (pintype "passive"))
      (node (ref "U5") (pin "B2") (pinfunction "VDDCORE_B2") (pintype "power_in"))
      (node (ref "U5") (pin "F15") (pinfunction "VDDCORE_F15") (pintype "power_in"))
      (node (ref "U5") (pin "F6") (pinfunction "VDDCORE_F6") (pintype "power_in"))
      (node (ref "U5") (pin "H3") (pinfunction "VDDCORE_H3") (pintype "power_in"))
      (node (ref "U5") (pin "J13") (pinfunction "VDDCORE_J13") (pintype "power_in"))
      (node (ref "U5") (pin "J16") (pinfunction "VDDCORE_J16") (pintype "power_in"))
      (node (ref "U5") (pin "J9") (pinfunction "VDDCORE_J9") (pintype "power_in"))
      (node (ref "U5") (pin "N13") (pinfunction "VDDCORE_N13") (pintype "power_in"))
      (node (ref "U5") (pin "N16") (pinfunction "VDDCORE_N16") (pintype "power_in"))
      (node (ref "U5") (pin "T15") (pinfunction "VDDCORE_T15") (pintype "power_in"))
      (node (ref "U5") (pin "U16") (pinfunction "VDDCORE_U16") (pintype "power_in"))
      (node (ref "U5") (pin "U17") (pinfunction "VDDCORE_U17") (pintype "power_in"))
      (node (ref "U5") (pin "U19") (pinfunction "VDDCORE_U19") (pintype "power_in"))
      (node (ref "U5") (pin "V19") (pinfunction "VDDCORE_V19") (pintype "power_in"))
    )
    (net (code "41") (name "VDDCPU") (class "Default")
      (node (ref "C32") (pin "1") (pinfunction "1_1") (pintype "passive"))
      (node (ref "C33") (pin "1") (pinfunction "1_1") (pintype "passive"))
      (node (ref "C34") (pin "1") (pinfunction "1_1") (pintype "passive"))
      (node (ref "C35") (pin "1") (pinfunction "1_1") (pintype "passive"))
      (node (ref "C36") (pin "1") (pinfunction "1_1") (pintype "passive"))
      (node (ref "C37") (pin "1") (pinfunction "1_1") (pintype "passive"))
      (node (ref "U5") (pin "B20") (pinfunction "VDDCPU_B20") (pintype "power_in"))
      (node (ref "U5") (pin "E16") (pinfunction "VDDCPU_E16") (pintype "power_in"))
      (node (ref "U5") (pin "E17") (pinfunction "VDDCPU_E17") (pintype "power_in"))
      (node (ref "U5") (pin "E19") (pinfunction "VDDCPU_E19") (pintype "power_in"))
      (node (ref "U5") (pin "F17") (pinfunction "VDDCPU_F17") (pintype "power_in"))
    )
    (net (code "42") (name "VDDOUT25") (class "Default")
      (node (ref "C66") (pin "2") (pinfunction "2_2") (pintype "passive"))
      (node (ref "C67") (pin "1") (pinfunction "1_1") (pintype "passive"))
      (node (ref "C68") (pin "1") (pinfunction "1_1") (pintype "passive"))
      (node (ref "C69") (pin "1") (pinfunction "1_1") (pintype "passive"))
      (node (ref "C70") (pin "1") (pinfunction "1_1") (pintype "passive"))
      (node (ref "C72") (pin "1") (pinfunction "1_1") (pintype "passive"))
      (node (ref "C73") (pin "1") (pinfunction "1_1") (pintype "passive"))
      (node (ref "U5") (pin "D2") (pinfunction "ADVREFP_D2") (pintype "power_in"))
      (node (ref "U5") (pin "E3") (pinfunction "VDDOUT25_E3") (pintype "power_in"))
      (node (ref "U5") (pin "E5") (pinfunction "VDDANA_E5") (pintype "power_in"))
      (node (ref "U5") (pin "J6") (pinfunction "VDDANA_J6") (pintype "power_in"))
      (node (ref "U5") (pin "T16") (pinfunction "VDDDPHY_T16") (pintype "power_in"))
      (node (ref "U5") (pin "W11") (pinfunction "VDDLVDS_W11") (pintype "power_in"))
      (node (ref "U5") (pin "W14") (pinfunction "VDDIN25_W14") (pintype "power_in"))
    )
    (net (code "43") (name "VDDSDMMC1") (class "Default")
      (node (ref "C59") (pin "1") (pinfunction "1_1") (pintype "passive"))
      (node (ref "U5") (pin "F9") (pinfunction "VDDSDMMC1_F9") (pintype "power_in"))
    )
    (net (code "44") (name "VDD_3V3") (class "Default")
      (node (ref "C54") (pin "1") (pinfunction "1_1") (pintype "passive"))
      (node (ref "C55") (pin "1") (pinfunction "1_1") (pintype "passive"))
      (node (ref "C56") (pin "1") (pinfunction "1_1") (pintype "passive"))
      (node (ref "C57") (pin "1") (pinfunction "1_1") (pintype "passive"))
      (node (ref "C58") (pin "1") (pinfunction "1_1") (pintype "passive"))
      (node (ref "C60") (pin "1") (pinfunction "1_1") (pintype "passive"))
      (node (ref "C61") (pin "1") (pinfunction "1_1") (pintype "passive"))
      (node (ref "C62") (pin "1") (pinfunction "1_1") (pintype "passive"))
      (node (ref "C63") (pin "2") (pinfunction "2_2") (pintype "passive"))
      (node (ref "C64") (pin "1") (pinfunction "1_1") (pintype "passive"))
      (node (ref "C75") (pin "2") (pinfunction "2_2") (pintype "passive"))
      (node (ref "R34") (pin "1") (pinfunction "1_1") (pintype "passive"))
      (node (ref "U5") (pin "C17") (pinfunction "VDDIOP1_C17") (pintype "power_in"))
      (node (ref "U5") (pin "F13") (pinfunction "VDDSDMMC2_F13") (pintype "power_in"))
      (node (ref "U5") (pin "G7") (pinfunction "VDDIN33_G7") (pintype "power_in"))
      (node (ref "U5") (pin "H19") (pinfunction "VDDGMAC1_H19") (pintype "power_in"))
      (node (ref "U5") (pin "L19") (pinfunction "VDDGMAC0_L19") (pintype "power_in"))
      (node (ref "U5") (pin "L3") (pinfunction "VDDUTMI_L3") (pintype "power_in"))
      (node (ref "U5") (pin "P19") (pinfunction "VDDQSPI0_P19") (pintype "power_in"))
      (node (ref "U5") (pin "T13") (pinfunction "VDDIOP0_T13") (pintype "power_in"))
      (node (ref "U5") (pin "W17") (pinfunction "VDDSDMMC0_W17") (pintype "power_in"))
      (node (ref "Y2") (pin "4") (pinfunction "VDD_4") (pintype "power_in"))
    )
  )
)
